# led-esp32s2.net
KiCad netlist of a schematic drawn in Altium Designer
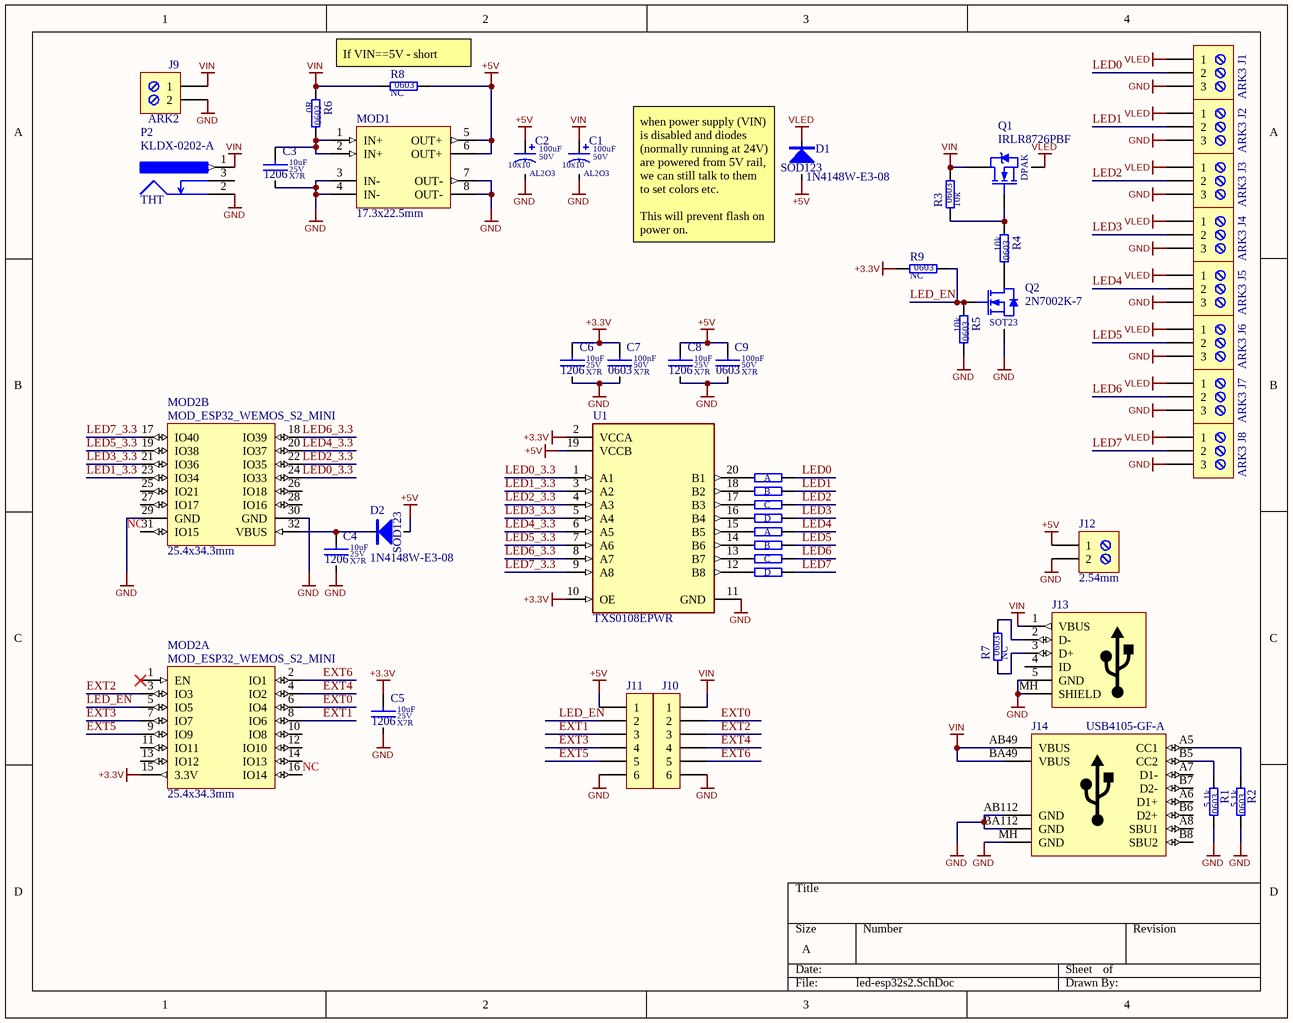
[diagram p0: led-esp32s2.SchDoc]

(export (version "E")
  (design (tool "Eeschema 10.0.6"))
  (components
    (comp (ref "C1")
      (value "100uF")
      (footprint "CE_D_10x10_SMD")
      (description "Polarized Capacitor")
      (fields
        (field (name "DIELECTRIC") "AL2O3")
        (field (name "SCH_FOOTPRINT") "10x10")
        (field (name "VOLTAGE") "50V")
        (field (name "PART NUMBER") "CE_100uF_50V_AL2O3_10x10_20")
        (field (name "MANUFACTURER") "Nichicon")
      )
      (libsource (lib "Library") (part "CE"))
    )
    (comp (ref "C2")
      (value "100uF")
      (footprint "CE_D_10x10_SMD")
      (description "Polarized Capacitor")
      (fields
        (field (name "DIELECTRIC") "AL2O3")
        (field (name "SCH_FOOTPRINT") "10x10")
        (field (name "VOLTAGE") "50V")
        (field (name "PART NUMBER") "CE_100uF_50V_AL2O3_10x10_20")
        (field (name "MANUFACTURER") "Nichicon")
      )
      (libsource (lib "Library") (part "CE"))
    )
    (comp (ref "C3")
      (value "10uF")
      (footprint "C_1206_3216")
      (description "Capacitor")
      (fields
        (field (name "DIELECTRIC") "X7R")
        (field (name "VOLTAGE") "25V")
        (field (name "SCH_FOOTPRINT") "1206")
        (field (name "PART NUMBER") "C_10uF_25V_X7R_1206_10")
        (field (name "MANUFACTURER") "Samsung")
      )
      (libsource (lib "Library") (part "C"))
    )
    (comp (ref "C4")
      (value "10uF")
      (footprint "C_1206_3216")
      (description "Capacitor")
      (fields
        (field (name "DIELECTRIC") "X7R")
        (field (name "VOLTAGE") "25V")
        (field (name "SCH_FOOTPRINT") "1206")
        (field (name "PART NUMBER") "C_10uF_25V_X7R_1206_10")
        (field (name "MANUFACTURER") "Samsung")
      )
      (libsource (lib "Library") (part "C"))
    )
    (comp (ref "C5")
      (value "10uF")
      (footprint "C_1206_3216")
      (description "Capacitor")
      (fields
        (field (name "DIELECTRIC") "X7R")
        (field (name "VOLTAGE") "25V")
        (field (name "SCH_FOOTPRINT") "1206")
        (field (name "PART NUMBER") "C_10uF_25V_X7R_1206_10")
        (field (name "MANUFACTURER") "Samsung")
      )
      (libsource (lib "Library") (part "C"))
    )
    (comp (ref "C6")
      (value "10uF")
      (footprint "C_1206_3216")
      (description "Capacitor")
      (fields
        (field (name "DIELECTRIC") "X7R")
        (field (name "VOLTAGE") "25V")
        (field (name "SCH_FOOTPRINT") "1206")
        (field (name "PART NUMBER") "C_10uF_25V_X7R_1206_10")
        (field (name "MANUFACTURER") "Samsung")
      )
      (libsource (lib "Library") (part "C"))
    )
    (comp (ref "C7")
      (value "100nF")
      (footprint "C_0603_1608")
      (description "Capacitor")
      (fields
        (field (name "DIELECTRIC") "X7R")
        (field (name "VOLTAGE") "50V")
        (field (name "SCH_FOOTPRINT") "0603")
        (field (name "PART NUMBER") "C_100nF_50V_X7R_0603_5")
        (field (name "MANUFACTURER") "Samsung")
      )
      (libsource (lib "Library") (part "C"))
    )
    (comp (ref "C8")
      (value "10uF")
      (footprint "C_1206_3216")
      (description "Capacitor")
      (fields
        (field (name "DIELECTRIC") "X7R")
        (field (name "VOLTAGE") "25V")
        (field (name "SCH_FOOTPRINT") "1206")
        (field (name "PART NUMBER") "C_10uF_25V_X7R_1206_10")
        (field (name "MANUFACTURER") "Samsung")
      )
      (libsource (lib "Library") (part "C"))
    )
    (comp (ref "C9")
      (value "100nF")
      (footprint "C_0603_1608")
      (description "Capacitor")
      (fields
        (field (name "DIELECTRIC") "X7R")
        (field (name "VOLTAGE") "50V")
        (field (name "SCH_FOOTPRINT") "0603")
        (field (name "PART NUMBER") "C_100nF_50V_X7R_0603_5")
        (field (name "MANUFACTURER") "Samsung")
      )
      (libsource (lib "Library") (part "C"))
    )
    (comp (ref "D1")
      (value "1N4148W-E3-08")
      (footprint "SOD123")
      (fields
        (field (name "SCH_FOOTPRINT") "SOD123")
        (field (name "PART NUMBER") "D_1N4148W_0A15_75V_SOD123")
        (field (name "VOLTAGE") "75")
        (field (name "MANUFACTURER") "Vishay")
      )
      (libsource (lib "Library") (part "D"))
    )
    (comp (ref "D2")
      (value "1N4148W-E3-08")
      (footprint "SOD123")
      (fields
        (field (name "SCH_FOOTPRINT") "SOD123")
        (field (name "PART NUMBER") "D_1N4148W_0A15_75V_SOD123")
        (field (name "VOLTAGE") "75")
        (field (name "MANUFACTURER") "Vishay")
      )
      (libsource (lib "Library") (part "D"))
    )
    (comp (ref "J1")
      (value "ARK3")
      (footprint "J_ARK3")
      (description "ARK Screw terminal, 3-Pin")
      (fields
        (field (name "SCH_FOOTPRINT") "ARK3")
        (field (name "PART NUMBER") "J_TB-5.0-P-3P")
        (field (name "MANUFACTURER") "DEGSON ELECTRONICS")
      )
      (libsource (lib "Library") (part "J_ARK3"))
    )
    (comp (ref "J2")
      (value "ARK3")
      (footprint "J_ARK3")
      (description "ARK Screw terminal, 3-Pin")
      (fields
        (field (name "SCH_FOOTPRINT") "ARK3")
        (field (name "PART NUMBER") "J_TB-5.0-P-3P")
        (field (name "MANUFACTURER") "DEGSON ELECTRONICS")
      )
      (libsource (lib "Library") (part "J_ARK3"))
    )
    (comp (ref "J3")
      (value "ARK3")
      (footprint "J_ARK3")
      (description "ARK Screw terminal, 3-Pin")
      (fields
        (field (name "SCH_FOOTPRINT") "ARK3")
        (field (name "PART NUMBER") "J_TB-5.0-P-3P")
        (field (name "MANUFACTURER") "DEGSON ELECTRONICS")
      )
      (libsource (lib "Library") (part "J_ARK3"))
    )
    (comp (ref "J4")
      (value "ARK3")
      (footprint "J_ARK3")
      (description "ARK Screw terminal, 3-Pin")
      (fields
        (field (name "SCH_FOOTPRINT") "ARK3")
        (field (name "PART NUMBER") "J_TB-5.0-P-3P")
        (field (name "MANUFACTURER") "DEGSON ELECTRONICS")
      )
      (libsource (lib "Library") (part "J_ARK3"))
    )
    (comp (ref "J5")
      (value "ARK3")
      (footprint "J_ARK3")
      (description "ARK Screw terminal, 3-Pin")
      (fields
        (field (name "SCH_FOOTPRINT") "ARK3")
        (field (name "PART NUMBER") "J_TB-5.0-P-3P")
        (field (name "MANUFACTURER") "DEGSON ELECTRONICS")
      )
      (libsource (lib "Library") (part "J_ARK3"))
    )
    (comp (ref "J6")
      (value "ARK3")
      (footprint "J_ARK3")
      (description "ARK Screw terminal, 3-Pin")
      (fields
        (field (name "SCH_FOOTPRINT") "ARK3")
        (field (name "PART NUMBER") "J_TB-5.0-P-3P")
        (field (name "MANUFACTURER") "DEGSON ELECTRONICS")
      )
      (libsource (lib "Library") (part "J_ARK3"))
    )
    (comp (ref "J7")
      (value "ARK3")
      (footprint "J_ARK3")
      (description "ARK Screw terminal, 3-Pin")
      (fields
        (field (name "SCH_FOOTPRINT") "ARK3")
        (field (name "PART NUMBER") "J_TB-5.0-P-3P")
        (field (name "MANUFACTURER") "DEGSON ELECTRONICS")
      )
      (libsource (lib "Library") (part "J_ARK3"))
    )
    (comp (ref "J8")
      (value "ARK3")
      (footprint "J_ARK3")
      (description "ARK Screw terminal, 3-Pin")
      (fields
        (field (name "SCH_FOOTPRINT") "ARK3")
        (field (name "PART NUMBER") "J_TB-5.0-P-3P")
        (field (name "MANUFACTURER") "DEGSON ELECTRONICS")
      )
      (libsource (lib "Library") (part "J_ARK3"))
    )
    (comp (ref "J9")
      (value "ARK2")
      (footprint "J_ARK2")
      (description "ARK Screw terminal, 2-Pin")
      (fields
        (field (name "SCH_FOOTPRINT") "ARK2")
        (field (name "PART NUMBER") "J_TB-5.0-P-2P")
        (field (name "MANUFACTURER") "DEGSON ELECTRONICS")
      )
      (libsource (lib "") (part "J_ARK2_1"))
    )
    (comp (ref "J10")
      (value "Goldpin female straight")
      (footprint "J_HEADER_1x6_2.54_VERTICAL")
      (description "Pin Header")
      (fields
        (field (name "PART NUMBER") "J_HEADER_1x6_2.54_VERTICAL")
        (field (name "MANUFACTURER") "Connfly")
      )
      (libsource (lib "Library") (part "J_HEADER_1x6"))
    )
    (comp (ref "J11")
      (value "Goldpin female straight")
      (footprint "J_HEADER_1x6_2.54_VERTICAL")
      (description "Pin Header")
      (fields
        (field (name "PART NUMBER") "J_HEADER_1x6_2.54_VERTICAL")
        (field (name "MANUFACTURER") "Connfly")
      )
      (libsource (lib "") (part "J_HEADER_1x6_1"))
    )
    (comp (ref "J12")
      (value "Fixed Terminal Blocks 2P 2.54mm 90DEG")
      (footprint "1725656")
      (description "ARK Screw terminal, 2-Pin")
      (fields
        (field (name "SCH_FOOTPRINT") "2.54mm")
        (field (name "PART NUMBER") "J_1725656")
        (field (name "MANUFACTURER") "Phoenix Contact")
      )
      (libsource (lib "Library") (part "J_ARK2"))
    )
    (comp (ref "J13")
      (value "USB connector")
      (footprint "J_USB_MINIB_54819-0519_THT")
      (description "USB A THT Connector")
      (fields (field (name "PART NUMBER") "J_USB_MINIB_54819-0519") (field (name "MANUFACTURER") "Molex"))
      (libsource (lib "Library") (part "J_USB_2.0_5pin"))
    )
    (comp (ref "J14")
      (value "USB4105-GF-A")
      (footprint "J_USB_C_USB4105")
      (fields
        (field (name "PART NUMBER") "J_USB_C_USB4105-GF-A")
        (field (name "MANUFACTURER") "GCT")
        (field (name "Comment") "USB C Connector")
      )
      (libsource (lib "Library") (part "J_USB_C_2.0_USB4105"))
    )
    (comp (ref "MOD1")
      (value "Low cost, Aliexpress-ready DC-DC buck converter using MP1584")
      (footprint "MOD_BUCK_MP1584")
      (fields (field (name "SCH_FOOTPRINT") "17.3x22.5mm") (field (name "PART NUMBER") "MOD_BUCK_MP1584"))
      (libsource (lib "Library") (part "MOD_BUCK_MP1584"))
    )
    (comp (ref "MOD2")
      (value "MOD_ESP32_WEMOS_S2_MINI")
      (footprint "MOD_ESP32_WEMOS_S2_MINI")
      (fields
        (field (name "SCH_FOOTPRINT") "25.4x34.3mm")
        (field (name "MANUFACTURER") "Wemos")
        (field (name "Comment") "ESP32-S2FN4R2 mini wifi board")
      )
      (libsource (lib "Library") (part "MOD_ESP32_WEMOS_S2_MINI"))
    )
    (comp (ref "P2")
      (value "KLDX-0202-A")
      (footprint "P_KLDX-0202-A")
      (description "Typical 3-pin jack power connector with switch")
      (fields
        (field (name "SCH_FOOTPRINT") "THT")
        (field (name "PART NUMBER") "P_KLDX-0202-A")
        (field (name "MANUFACTURER") "Kycon")
      )
      (libsource (lib "Library") (part "P_DC_JACK"))
    )
    (comp (ref "Q1")
      (value "IRLR8726PBF")
      (footprint "DPAK_TO252-3_SC63_M")
      (fields
        (field (name "SCH_FOOTPRINT") "DPAK")
        (field (name "PART NUMBER") "QNS_IRLR8726PBF")
        (field (name "VOLTAGE") "30V")
        (field (name "MANUFACTURER") "Infineon")
      )
      (libsource (lib "Library") (part "QNS_GDS"))
    )
    (comp (ref "Q2")
      (value "2N7002K-7")
      (footprint "SOT23_TO236_SC59")
      (fields
        (field (name "SCH_FOOTPRINT") "SOT23")
        (field (name "PART NUMBER") "QN_2N7002K-7")
        (field (name "VOLTAGE") "60V")
        (field (name "MANUFACTURER") "Diodes Inc")
      )
      (libsource (lib "Library") (part "QN_GSD"))
    )
    (comp (ref "R1")
      (value "5.1k")
      (footprint "R_0603_1608")
      (fields
        (field (name "SCH_FOOTPRINT") "0603")
        (field (name "PART NUMBER") "R_5.1k_0603_1")
        (field (name "VOLTAGE") "75V")
        (field (name "POWER") "100mW")
      )
      (libsource (lib "Library") (part "R"))
    )
    (comp (ref "R2")
      (value "5.1k")
      (footprint "R_0603_1608")
      (fields
        (field (name "SCH_FOOTPRINT") "0603")
        (field (name "PART NUMBER") "R_5.1k_0603_1")
        (field (name "VOLTAGE") "75V")
        (field (name "POWER") "100mW")
      )
      (libsource (lib "Library") (part "R"))
    )
    (comp (ref "R3")
      (value "10k")
      (footprint "R_0603_1608")
      (fields
        (field (name "SCH_FOOTPRINT") "0603")
        (field (name "PART NUMBER") "R_10k_0603_1")
        (field (name "VOLTAGE") "75V")
        (field (name "POWER") "100mW")
      )
      (libsource (lib "Library") (part "R"))
    )
    (comp (ref "R4")
      (value "10k")
      (footprint "R_0603_1608")
      (fields
        (field (name "SCH_FOOTPRINT") "0603")
        (field (name "PART NUMBER") "R_10k_0603_1")
        (field (name "VOLTAGE") "75V")
        (field (name "POWER") "100mW")
      )
      (libsource (lib "Library") (part "R"))
    )
    (comp (ref "R5")
      (value "10k")
      (footprint "R_0603_1608")
      (fields
        (field (name "SCH_FOOTPRINT") "0603")
        (field (name "PART NUMBER") "R_10k_0603_1")
        (field (name "VOLTAGE") "75V")
        (field (name "POWER") "100mW")
      )
      (libsource (lib "Library") (part "R"))
    )
    (comp (ref "R6")
      (value "0R")
      (footprint "R_0603_1608")
      (fields
        (field (name "SCH_FOOTPRINT") "0603")
        (field (name "PART NUMBER") "R_0R_0603_1")
        (field (name "VOLTAGE") "75V")
        (field (name "POWER") "100mW")
      )
      (libsource (lib "Library") (part "R"))
    )
    (comp (ref "R7")
      (value "NC")
      (footprint "R_NC_0603_1608")
      (fields
        (field (name "SCH_FOOTPRINT") "0603")
        (field (name "PART NUMBER") "R_GENERIC_0603")
        (field (name "Comment") "Resistor")
      )
      (libsource (lib "Library") (part "R"))
    )
    (comp (ref "R8")
      (value "NC")
      (footprint "R_NC_0603_1608")
      (fields
        (field (name "SCH_FOOTPRINT") "0603")
        (field (name "PART NUMBER") "R_GENERIC_0603")
        (field (name "Comment") "Resistor")
      )
      (libsource (lib "Library") (part "R"))
    )
    (comp (ref "R9")
      (value "NC")
      (footprint "R_NC_0603_1608")
      (fields
        (field (name "SCH_FOOTPRINT") "0603")
        (field (name "PART NUMBER") "R_GENERIC_0603")
        (field (name "Comment") "Resistor")
      )
      (libsource (lib "Library") (part "R"))
    )
    (comp (ref "RN1")
      (value "Resistors Network")
      (footprint "RN4_0804_2010")
      (fields
        (field (name "PART NUMBER") "RN4_120R_0804_5")
        (field (name "VOLTAGE") "50V")
        (field (name "POWER") "63mW")
      )
      (libsource (lib "Library") (part "RN4"))
    )
    (comp (ref "RN2")
      (value "Resistors Network")
      (footprint "RN4_0804_2010")
      (fields
        (field (name "PART NUMBER") "RN4_120R_0804_5")
        (field (name "VOLTAGE") "50V")
        (field (name "POWER") "63mW")
      )
      (libsource (lib "Library") (part "RN4"))
    )
    (comp (ref "U1")
      (value "TXS0108EPWR")
      (footprint "FP-PW0020A-IPC_C")
      (description "IC TRNSLTR BIDIRECTIONAL 20TSSOP")
      (libsource (lib "Altium Content Vault") (part "86128ddf5852d4e934b2dd0188c13f1"))
    )
  )
  (nets
    (net (code "1") (name "+3.3V") (class "Default")
      (node (ref "C5") (pin "1") (pinfunction "1_1") (pintype "passive"))
      (node (ref "C6") (pin "1") (pinfunction "1_1") (pintype "passive"))
      (node (ref "C7") (pin "1") (pinfunction "1_1") (pintype "passive"))
      (node (ref "MOD2") (pin "15") (pinfunction "3.3V_15") (pintype "output"))
      (node (ref "R9") (pin "1") (pinfunction "1_1") (pintype "passive"))
      (node (ref "U1") (pin "10") (pinfunction "OE_10") (pintype "input"))
      (node (ref "U1") (pin "2") (pinfunction "VCCA_2") (pintype "power_in"))
    )
    (net (code "2") (name "+5V") (class "Default")
      (node (ref "C2") (pin "1") (pinfunction "1_1") (pintype "passive"))
      (node (ref "C8") (pin "1") (pinfunction "1_1") (pintype "passive"))
      (node (ref "C9") (pin "1") (pinfunction "1_1") (pintype "passive"))
      (node (ref "D1") (pin "2") (pintype "passive"))
      (node (ref "D2") (pin "2") (pintype "passive"))
      (node (ref "J11") (pin "1") (pinfunction "1_1") (pintype "passive"))
      (node (ref "J12") (pin "1") (pinfunction "1_1") (pintype "passive"))
      (node (ref "MOD1") (pin "5") (pinfunction "OUT+_5") (pintype "output"))
      (node (ref "MOD1") (pin "6") (pinfunction "OUT+_6") (pintype "passive"))
      (node (ref "R8") (pin "2") (pinfunction "2_2") (pintype "passive"))
      (node (ref "U1") (pin "19") (pinfunction "VCCB_19") (pintype "power_in"))
    )
    (net (code "3") (name "/EXT0") (class "Default")
      (node (ref "J10") (pin "2") (pinfunction "2_2") (pintype "passive"))
      (node (ref "MOD2") (pin "6") (pinfunction "IO4_6") (pintype "bidirectional"))
    )
    (net (code "4") (name "/EXT1") (class "Default")
      (node (ref "J11") (pin "3") (pinfunction "3_3") (pintype "passive"))
      (node (ref "MOD2") (pin "8") (pinfunction "IO6_8") (pintype "bidirectional"))
    )
    (net (code "5") (name "/EXT2") (class "Default")
      (node (ref "J10") (pin "3") (pinfunction "3_3") (pintype "passive"))
      (node (ref "MOD2") (pin "3") (pinfunction "IO3_3") (pintype "bidirectional"))
    )
    (net (code "6") (name "/EXT3") (class "Default")
      (node (ref "J11") (pin "4") (pinfunction "4_4") (pintype "passive"))
      (node (ref "MOD2") (pin "7") (pinfunction "IO7_7") (pintype "bidirectional"))
    )
    (net (code "7") (name "/EXT4") (class "Default")
      (node (ref "J10") (pin "4") (pinfunction "4_4") (pintype "passive"))
      (node (ref "MOD2") (pin "4") (pinfunction "IO2_4") (pintype "bidirectional"))
    )
    (net (code "8") (name "/EXT5") (class "Default")
      (node (ref "J11") (pin "5") (pinfunction "5_5") (pintype "passive"))
      (node (ref "MOD2") (pin "9") (pinfunction "IO9_9") (pintype "bidirectional"))
    )
    (net (code "9") (name "/EXT6") (class "Default")
      (node (ref "J10") (pin "5") (pinfunction "5_5") (pintype "passive"))
      (node (ref "MOD2") (pin "2") (pinfunction "IO1_2") (pintype "bidirectional"))
    )
    (net (code "10") (name "/LED0") (class "Default")
      (node (ref "J1") (pin "2") (pinfunction "2_2") (pintype "passive"))
      (node (ref "RN1") (pin "8") (pinfunction "8_8") (pintype "passive"))
    )
    (net (code "11") (name "/LED0_3.3") (class "Default")
      (node (ref "MOD2") (pin "24") (pinfunction "IO33_24") (pintype "bidirectional"))
      (node (ref "U1") (pin "1") (pinfunction "A1_1") (pintype "input"))
    )
    (net (code "12") (name "/LED1") (class "Default")
      (node (ref "J2") (pin "2") (pinfunction "2_2") (pintype "passive"))
      (node (ref "RN1") (pin "7") (pinfunction "7_7") (pintype "passive"))
    )
    (net (code "13") (name "/LED1_3.3") (class "Default")
      (node (ref "MOD2") (pin "23") (pinfunction "IO34_23") (pintype "bidirectional"))
      (node (ref "U1") (pin "3") (pinfunction "A2_3") (pintype "input"))
    )
    (net (code "14") (name "/LED2") (class "Default")
      (node (ref "J3") (pin "2") (pinfunction "2_2") (pintype "passive"))
      (node (ref "RN1") (pin "6") (pinfunction "6_6") (pintype "passive"))
    )
    (net (code "15") (name "/LED2_3.3") (class "Default")
      (node (ref "MOD2") (pin "22") (pinfunction "IO35_22") (pintype "bidirectional"))
      (node (ref "U1") (pin "4") (pinfunction "A3_4") (pintype "input"))
    )
    (net (code "16") (name "/LED3") (class "Default")
      (node (ref "J4") (pin "2") (pinfunction "2_2") (pintype "passive"))
      (node (ref "RN1") (pin "5") (pinfunction "5_5") (pintype "passive"))
    )
    (net (code "17") (name "/LED3_3.3") (class "Default")
      (node (ref "MOD2") (pin "21") (pinfunction "IO36_21") (pintype "bidirectional"))
      (node (ref "U1") (pin "5") (pinfunction "A4_5") (pintype "input"))
    )
    (net (code "18") (name "/LED4") (class "Default")
      (node (ref "J5") (pin "2") (pinfunction "2_2") (pintype "passive"))
      (node (ref "RN2") (pin "8") (pinfunction "8_8") (pintype "passive"))
    )
    (net (code "19") (name "/LED4_3.3") (class "Default")
      (node (ref "MOD2") (pin "20") (pinfunction "IO37_20") (pintype "bidirectional"))
      (node (ref "U1") (pin "6") (pinfunction "A5_6") (pintype "input"))
    )
    (net (code "20") (name "/LED5") (class "Default")
      (node (ref "J6") (pin "2") (pinfunction "2_2") (pintype "passive"))
      (node (ref "RN2") (pin "7") (pinfunction "7_7") (pintype "passive"))
    )
    (net (code "21") (name "/LED5_3.3") (class "Default")
      (node (ref "MOD2") (pin "19") (pinfunction "IO38_19") (pintype "bidirectional"))
      (node (ref "U1") (pin "7") (pinfunction "A6_7") (pintype "input"))
    )
    (net (code "22") (name "/LED6") (class "Default")
      (node (ref "J7") (pin "2") (pinfunction "2_2") (pintype "passive"))
      (node (ref "RN2") (pin "6") (pinfunction "6_6") (pintype "passive"))
    )
    (net (code "23") (name "/LED6_3.3") (class "Default")
      (node (ref "MOD2") (pin "18") (pinfunction "IO39_18") (pintype "bidirectional"))
      (node (ref "U1") (pin "8") (pinfunction "A7_8") (pintype "input"))
    )
    (net (code "24") (name "/LED7") (class "Default")
      (node (ref "J8") (pin "2") (pinfunction "2_2") (pintype "passive"))
      (node (ref "RN2") (pin "5") (pinfunction "5_5") (pintype "passive"))
    )
    (net (code "25") (name "/LED7_3.3") (class "Default")
      (node (ref "MOD2") (pin "17") (pinfunction "IO40_17") (pintype "bidirectional"))
      (node (ref "U1") (pin "9") (pinfunction "A8_9") (pintype "input"))
    )
    (net (code "26") (name "/LED_EN") (class "Default")
      (node (ref "J11") (pin "2") (pinfunction "2_2") (pintype "passive"))
      (node (ref "MOD2") (pin "5") (pinfunction "IO5_5") (pintype "bidirectional"))
      (node (ref "Q2") (pin "1") (pinfunction "G_1") (pintype "passive"))
      (node (ref "R5") (pin "1") (pinfunction "1_1") (pintype "passive"))
      (node (ref "R9") (pin "2") (pinfunction "2_2") (pintype "passive"))
    )
    (net (code "27") (name "GND") (class "Default")
      (node (ref "C1") (pin "2") (pinfunction "2_2") (pintype "passive"))
      (node (ref "C2") (pin "2") (pinfunction "2_2") (pintype "passive"))
      (node (ref "C3") (pin "2") (pinfunction "2_2") (pintype "passive"))
      (node (ref "C4") (pin "2") (pinfunction "2_2") (pintype "passive"))
      (node (ref "C5") (pin "2") (pinfunction "2_2") (pintype "passive"))
      (node (ref "C6") (pin "2") (pinfunction "2_2") (pintype "passive"))
      (node (ref "C7") (pin "2") (pinfunction "2_2") (pintype "passive"))
      (node (ref "C8") (pin "2") (pinfunction "2_2") (pintype "passive"))
      (node (ref "C9") (pin "2") (pinfunction "2_2") (pintype "passive"))
      (node (ref "J1") (pin "3") (pinfunction "3_3") (pintype "passive"))
      (node (ref "J10") (pin "6") (pinfunction "6_6") (pintype "passive"))
      (node (ref "J11") (pin "6") (pinfunction "6_6") (pintype "passive"))
      (node (ref "J12") (pin "2") (pinfunction "2_2") (pintype "passive"))
      (node (ref "J13") (pin "5") (pinfunction "GND_5") (pintype "power_in"))
      (node (ref "J13") (pin "MH") (pinfunction "SHIELD_MH") (pintype "passive"))
      (node (ref "J14") (pin "AB112") (pinfunction "GND_AB112") (pintype "power_in"))
      (node (ref "J14") (pin "BA112") (pinfunction "GND_BA112") (pintype "power_in"))
      (node (ref "J14") (pin "MH") (pinfunction "GND_MH") (pintype "power_in"))
      (node (ref "J2") (pin "3") (pinfunction "3_3") (pintype "passive"))
      (node (ref "J3") (pin "3") (pinfunction "3_3") (pintype "passive"))
      (node (ref "J4") (pin "3") (pinfunction "3_3") (pintype "passive"))
      (node (ref "J5") (pin "3") (pinfunction "3_3") (pintype "passive"))
      (node (ref "J6") (pin "3") (pinfunction "3_3") (pintype "passive"))
      (node (ref "J7") (pin "3") (pinfunction "3_3") (pintype "passive"))
      (node (ref "J8") (pin "3") (pinfunction "3_3") (pintype "passive"))
      (node (ref "J9") (pin "2") (pinfunction "2_2") (pintype "passive"))
      (node (ref "MOD1") (pin "3") (pinfunction "IN-_3") (pintype "power_in"))
      (node (ref "MOD1") (pin "4") (pinfunction "IN-_4") (pintype "power_in"))
      (node (ref "MOD1") (pin "7") (pinfunction "OUT-_7") (pintype "output"))
      (node (ref "MOD1") (pin "8") (pinfunction "OUT-_8") (pintype "passive"))
      (node (ref "MOD2") (pin "29") (pinfunction "GND_29") (pintype "power_in"))
      (node (ref "MOD2") (pin "30") (pinfunction "GND_30") (pintype "power_in"))
      (node (ref "P2") (pin "2") (pinfunction "2_2") (pintype "passive"))
      (node (ref "Q2") (pin "2") (pinfunction "S_2") (pintype "passive"))
      (node (ref "R1") (pin "2") (pinfunction "2_2") (pintype "passive"))
      (node (ref "R2") (pin "2") (pinfunction "2_2") (pintype "passive"))
      (node (ref "R5") (pin "2") (pinfunction "2_2") (pintype "passive"))
      (node (ref "U1") (pin "11") (pinfunction "GND_11") (pintype "power_in"))
    )
    (net (code "28") (name "Net-(C3-Pad1)") (class "Default")
      (node (ref "C3") (pin "1") (pinfunction "1_1") (pintype "passive"))
      (node (ref "MOD1") (pin "1") (pinfunction "IN+_1") (pintype "input"))
      (node (ref "MOD1") (pin "2") (pinfunction "IN+_2") (pintype "input"))
      (node (ref "R6") (pin "2") (pinfunction "2_2") (pintype "passive"))
    )
    (net (code "29") (name "Net-(J13-D+)") (class "Default")
      (node (ref "J13") (pin "3") (pinfunction "D+_3") (pintype "bidirectional"))
      (node (ref "R7") (pin "1") (pinfunction "1_1") (pintype "passive"))
    )
    (net (code "30") (name "Net-(J13-D-)") (class "Default")
      (node (ref "J13") (pin "2") (pinfunction "D-_2") (pintype "bidirectional"))
      (node (ref "R7") (pin "2") (pinfunction "2_2") (pintype "passive"))
    )
    (net (code "31") (name "Net-(J14-CC1)") (class "Default")
      (node (ref "J14") (pin "A5") (pinfunction "CC1_A5") (pintype "bidirectional"))
      (node (ref "R2") (pin "1") (pinfunction "1_1") (pintype "passive"))
    )
    (net (code "32") (name "Net-(J14-CC2)") (class "Default")
      (node (ref "J14") (pin "B5") (pinfunction "CC2_B5") (pintype "bidirectional"))
      (node (ref "R1") (pin "1") (pinfunction "1_1") (pintype "passive"))
    )
    (net (code "33") (name "Net-(MOD2B-VBUS)") (class "Default")
      (node (ref "C4") (pin "1") (pinfunction "1_1") (pintype "passive"))
      (node (ref "D2") (pin "1") (pintype "passive"))
      (node (ref "MOD2") (pin "32") (pinfunction "VBUS_32") (pintype "bidirectional"))
    )
    (net (code "34") (name "Net-(Q1-G)") (class "Default")
      (node (ref "Q1") (pin "1") (pinfunction "G_1") (pintype "passive"))
      (node (ref "R3") (pin "1") (pinfunction "1_1") (pintype "passive"))
      (node (ref "R4") (pin "1") (pinfunction "1_1") (pintype "passive"))
    )
    (net (code "35") (name "Net-(Q2-D)") (class "Default")
      (node (ref "Q2") (pin "3") (pinfunction "D_3") (pintype "passive"))
      (node (ref "R4") (pin "2") (pinfunction "2_2") (pintype "passive"))
    )
    (net (code "36") (name "Net-(U1-B1)") (class "Default")
      (node (ref "RN1") (pin "1") (pinfunction "1_1") (pintype "passive"))
      (node (ref "U1") (pin "20") (pinfunction "B1_20") (pintype "output"))
    )
    (net (code "37") (name "Net-(U1-B2)") (class "Default")
      (node (ref "RN1") (pin "2") (pinfunction "2_2") (pintype "passive"))
      (node (ref "U1") (pin "18") (pinfunction "B2_18") (pintype "output"))
    )
    (net (code "38") (name "Net-(U1-B3)") (class "Default")
      (node (ref "RN1") (pin "3") (pinfunction "3_3") (pintype "passive"))
      (node (ref "U1") (pin "17") (pinfunction "B3_17") (pintype "output"))
    )
    (net (code "39") (name "Net-(U1-B4)") (class "Default")
      (node (ref "RN1") (pin "4") (pinfunction "4_4") (pintype "passive"))
      (node (ref "U1") (pin "16") (pinfunction "B4_16") (pintype "output"))
    )
    (net (code "40") (name "Net-(U1-B5)") (class "Default")
      (node (ref "RN2") (pin "1") (pinfunction "1_1") (pintype "passive"))
      (node (ref "U1") (pin "15") (pinfunction "B5_15") (pintype "output"))
    )
    (net (code "41") (name "Net-(U1-B6)") (class "Default")
      (node (ref "RN2") (pin "2") (pinfunction "2_2") (pintype "passive"))
      (node (ref "U1") (pin "14") (pinfunction "B6_14") (pintype "output"))
    )
    (net (code "42") (name "Net-(U1-B7)") (class "Default")
      (node (ref "RN2") (pin "3") (pinfunction "3_3") (pintype "passive"))
      (node (ref "U1") (pin "13") (pinfunction "B7_13") (pintype "output"))
    )
    (net (code "43") (name "Net-(U1-B8)") (class "Default")
      (node (ref "RN2") (pin "4") (pinfunction "4_4") (pintype "passive"))
      (node (ref "U1") (pin "12") (pinfunction "B8_12") (pintype "output"))
    )
    (net (code "44") (name "VIN") (class "Default")
      (node (ref "C1") (pin "1") (pinfunction "1_1") (pintype "passive"))
      (node (ref "J10") (pin "1") (pinfunction "1_1") (pintype "passive"))
      (node (ref "J13") (pin "1") (pinfunction "VBUS_1") (pintype "output"))
      (node (ref "J14") (pin "AB49") (pinfunction "VBUS_AB49") (pintype "power_in"))
      (node (ref "J14") (pin "BA49") (pinfunction "VBUS_BA49") (pintype "power_in"))
      (node (ref "J9") (pin "1") (pinfunction "1_1") (pintype "passive"))
      (node (ref "P2") (pin "1") (pinfunction "1_1") (pintype "output"))
      (node (ref "Q1") (pin "2") (pinfunction "D_2") (pintype "passive"))
      (node (ref "R3") (pin "2") (pinfunction "2_2") (pintype "passive"))
      (node (ref "R6") (pin "1") (pinfunction "1_1") (pintype "passive"))
      (node (ref "R8") (pin "1") (pinfunction "1_1") (pintype "passive"))
    )
    (net (code "45") (name "VLED") (class "Default")
      (node (ref "D1") (pin "1") (pintype "passive"))
      (node (ref "J1") (pin "1") (pinfunction "1_1") (pintype "passive"))
      (node (ref "J2") (pin "1") (pinfunction "1_1") (pintype "passive"))
      (node (ref "J3") (pin "1") (pinfunction "1_1") (pintype "passive"))
      (node (ref "J4") (pin "1") (pinfunction "1_1") (pintype "passive"))
      (node (ref "J5") (pin "1") (pinfunction "1_1") (pintype "passive"))
      (node (ref "J6") (pin "1") (pinfunction "1_1") (pintype "passive"))
      (node (ref "J7") (pin "1") (pinfunction "1_1") (pintype "passive"))
      (node (ref "J8") (pin "1") (pinfunction "1_1") (pintype "passive"))
      (node (ref "Q1") (pin "3") (pinfunction "S_3") (pintype "passive"))
    )
    (net (code "46") (name "unconnected-(J13-ID-Pad4)") (class "Default")
      (node (ref "J13") (pin "4") (pinfunction "ID_4") (pintype "power_in"))
    )
    (net (code "47") (name "unconnected-(J14-D1+-PadA6)") (class "Default")
      (node (ref "J14") (pin "A6") (pinfunction "D1+_A6") (pintype "bidirectional"))
    )
    (net (code "48") (name "unconnected-(J14-D1--PadA7)") (class "Default")
      (node (ref "J14") (pin "A7") (pinfunction "D1-_A7") (pintype "bidirectional"))
    )
    (net (code "49") (name "unconnected-(J14-D2+-PadB6)") (class "Default")
      (node (ref "J14") (pin "B6") (pinfunction "D2+_B6") (pintype "bidirectional"))
    )
    (net (code "50") (name "unconnected-(J14-D2--PadB7)") (class "Default")
      (node (ref "J14") (pin "B7") (pinfunction "D2-_B7") (pintype "bidirectional"))
    )
    (net (code "51") (name "unconnected-(J14-SBU1-PadA8)") (class "Default")
      (node (ref "J14") (pin "A8") (pinfunction "SBU1_A8") (pintype "bidirectional"))
    )
    (net (code "52") (name "unconnected-(J14-SBU2-PadB8)") (class "Default")
      (node (ref "J14") (pin "B8") (pinfunction "SBU2_B8") (pintype "bidirectional"))
    )
    (net (code "53") (name "unconnected-(MOD2A-EN-Pad1)") (class "Default")
      (node (ref "MOD2") (pin "1") (pinfunction "EN_1") (pintype "input+no_connect"))
    )
    (net (code "54") (name "unconnected-(MOD2A-IO8-Pad10)") (class "Default")
      (node (ref "MOD2") (pin "10") (pinfunction "IO8_10") (pintype "bidirectional"))
    )
    (net (code "55") (name "unconnected-(MOD2A-IO10-Pad12)") (class "Default")
      (node (ref "MOD2") (pin "12") (pinfunction "IO10_12") (pintype "bidirectional"))
    )
    (net (code "56") (name "unconnected-(MOD2A-IO11-Pad11)") (class "Default")
      (node (ref "MOD2") (pin "11") (pinfunction "IO11_11") (pintype "bidirectional"))
    )
    (net (code "57") (name "unconnected-(MOD2A-IO12-Pad13)") (class "Default")
      (node (ref "MOD2") (pin "13") (pinfunction "IO12_13") (pintype "bidirectional"))
    )
    (net (code "58") (name "unconnected-(MOD2A-IO13-Pad14)") (class "Default")
      (node (ref "MOD2") (pin "14") (pinfunction "IO13_14") (pintype "bidirectional"))
    )
    (net (code "59") (name "unconnected-(MOD2A-IO14-Pad16)") (class "Default")
      (node (ref "MOD2") (pin "16") (pinfunction "IO14_16") (pintype "bidirectional"))
    )
    (net (code "60") (name "unconnected-(MOD2B-IO15-Pad31)") (class "Default")
      (node (ref "MOD2") (pin "31") (pinfunction "IO15_31") (pintype "bidirectional"))
    )
    (net (code "61") (name "unconnected-(MOD2B-IO16-Pad28)") (class "Default")
      (node (ref "MOD2") (pin "28") (pinfunction "IO16_28") (pintype "bidirectional"))
    )
    (net (code "62") (name "unconnected-(MOD2B-IO17-Pad27)") (class "Default")
      (node (ref "MOD2") (pin "27") (pinfunction "IO17_27") (pintype "bidirectional"))
    )
    (net (code "63") (name "unconnected-(MOD2B-IO18-Pad26)") (class "Default")
      (node (ref "MOD2") (pin "26") (pinfunction "IO18_26") (pintype "bidirectional"))
    )
    (net (code "64") (name "unconnected-(MOD2B-IO21-Pad25)") (class "Default")
      (node (ref "MOD2") (pin "25") (pinfunction "IO21_25") (pintype "bidirectional"))
    )
    (net (code "65") (name "unconnected-(P2-Pad3)") (class "Default")
      (node (ref "P2") (pin "3") (pinfunction "3_3") (pintype "passive"))
    )
  )
)
